# Project.net
KiCad netlist of a schematic drawn in EAGLE
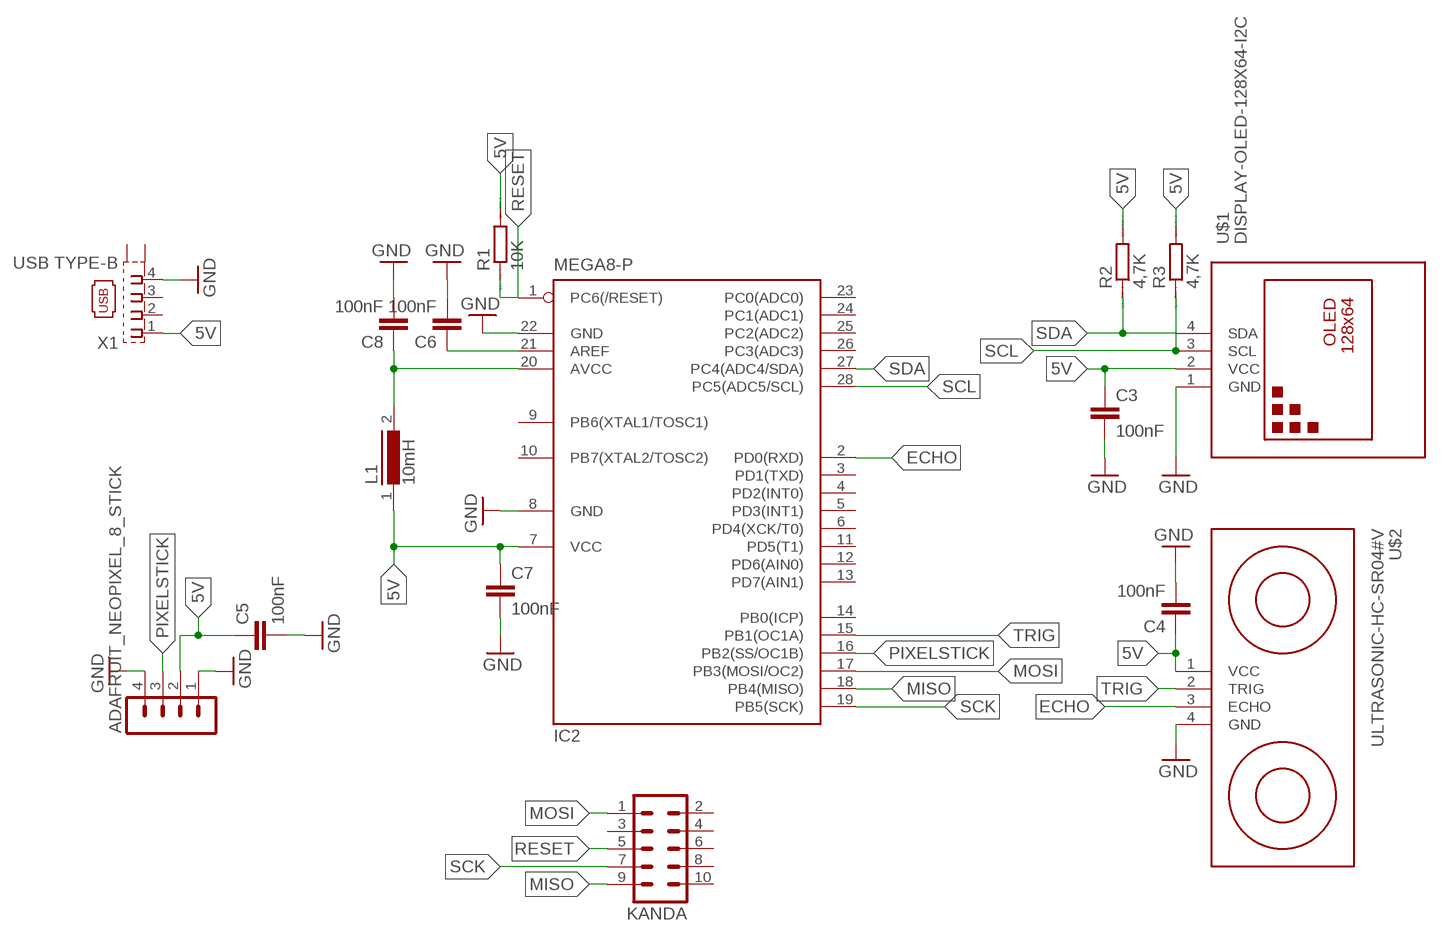
[diagram p0: schematic, sheet 1]

(export (version "E")
  (design (tool "Eeschema 10.0.6"))
  (components
    (comp (ref "ADAFRUIT_NEOPIXEL_8_STICK")
      (value "MA04-1")
      (footprint "eagle-import:MA04-1")
      (libsource (lib "eagle-import") (part "MA04-1"))
    )
    (comp (ref "C3")
      (value "100nF")
      (footprint "eagle-import:C025-024X044")
      (libsource (lib "eagle-import") (part "C-EU025-024X044"))
    )
    (comp (ref "C4")
      (value "100nF")
      (footprint "eagle-import:C025-024X044")
      (libsource (lib "eagle-import") (part "C-EU025-024X044"))
    )
    (comp (ref "C5")
      (value "100nF")
      (footprint "eagle-import:C025-024X044")
      (libsource (lib "eagle-import") (part "C-EU025-024X044"))
    )
    (comp (ref "C6")
      (value "100nF")
      (footprint "eagle-import:C025-024X044")
      (libsource (lib "eagle-import") (part "C-EU025-024X044"))
    )
    (comp (ref "C7")
      (value "100nF")
      (footprint "eagle-import:C025-024X044")
      (libsource (lib "eagle-import") (part "C-EU025-024X044"))
    )
    (comp (ref "C8")
      (value "100nF")
      (footprint "eagle-import:C025-024X044")
      (libsource (lib "eagle-import") (part "C-EU025-024X044"))
    )
    (comp (ref "IC2")
      (value "MEGA8-P")
      (footprint "eagle-import:DIL28-3")
      (libsource (lib "eagle-import") (part "MEGA8-P"))
    )
    (comp (ref "KANDA")
      (value "ML10")
      (footprint "eagle-import:ML10")
      (libsource (lib "eagle-import") (part "ML10"))
    )
    (comp (ref "L1")
      (value "10mH")
      (footprint "eagle-import:A26GFC")
      (libsource (lib "eagle-import") (part "A26GFC"))
    )
    (comp (ref "R1")
      (value "10K")
      (footprint "eagle-import:R0805")
      (libsource (lib "eagle-import") (part "R"))
    )
    (comp (ref "R2")
      (value "4,7K")
      (footprint "eagle-import:R0805")
      (libsource (lib "eagle-import") (part "R"))
    )
    (comp (ref "R3")
      (value "4,7K")
      (footprint "eagle-import:R0805")
      (libsource (lib "eagle-import") (part "R"))
    )
    (comp (ref "U$1")
      (value "DISPLAY-OLED-128X64-I2C")
      (footprint "eagle-import:DISPLAY-OLED-128X64-I2C")
      (libsource (lib "eagle-import") (part "DISPLAY-OLED-128X64-I2C"))
    )
    (comp (ref "U$2")
      (value "ULTRASONIC-HC-SR04#V")
      (footprint "eagle-import:ULTRASONIC-HC-SR04#V")
      (libsource (lib "eagle-import") (part "ULTRASONIC-HC-SR04#V"))
    )
    (comp (ref "X1")
      (value "USB TYPE-B")
      (footprint "eagle-import:KUSBVX-BS1N")
      (libsource (lib "eagle-import") (part "KUSBVX-BS1N"))
    )
  )
  (nets
    (net (code "1") (name "5V") (class "Default")
      (node (ref "ADAFRUIT_NEOPIXEL_8_STICK") (pin "2") (pinfunction "2_2") (pintype "passive"))
      (node (ref "C3") (pin "1") (pinfunction "1_1") (pintype "passive"))
      (node (ref "C4") (pin "1") (pinfunction "1_1") (pintype "passive"))
      (node (ref "C5") (pin "1") (pinfunction "1_1") (pintype "passive"))
      (node (ref "C7") (pin "1") (pinfunction "1_1") (pintype "passive"))
      (node (ref "IC2") (pin "7") (pinfunction "VCC_7") (pintype "power_in"))
      (node (ref "L1") (pin "1") (pinfunction "1_1") (pintype "passive"))
      (node (ref "R1") (pin "2") (pinfunction "2_2") (pintype "passive"))
      (node (ref "R2") (pin "2") (pinfunction "2_2") (pintype "passive"))
      (node (ref "R3") (pin "2") (pinfunction "2_2") (pintype "passive"))
      (node (ref "U$1") (pin "2") (pinfunction "VCC_2") (pintype "power_in"))
      (node (ref "U$2") (pin "1") (pinfunction "VCC_1") (pintype "power_in"))
      (node (ref "X1") (pin "1") (pinfunction "1_1") (pintype "passive"))
    )
    (net (code "2") (name "ECHO") (class "Default")
      (node (ref "IC2") (pin "2") (pinfunction "PD0(RXD)_2") (pintype "bidirectional"))
      (node (ref "U$2") (pin "3") (pinfunction "ECHO_3") (pintype "output"))
    )
    (net (code "3") (name "GND") (class "Default")
      (node (ref "ADAFRUIT_NEOPIXEL_8_STICK") (pin "1") (pinfunction "1_1") (pintype "passive"))
      (node (ref "ADAFRUIT_NEOPIXEL_8_STICK") (pin "4") (pinfunction "4_4") (pintype "passive"))
      (node (ref "C3") (pin "2") (pinfunction "2_2") (pintype "passive"))
      (node (ref "C4") (pin "2") (pinfunction "2_2") (pintype "passive"))
      (node (ref "C5") (pin "2") (pinfunction "2_2") (pintype "passive"))
      (node (ref "C6") (pin "2") (pinfunction "2_2") (pintype "passive"))
      (node (ref "C7") (pin "2") (pinfunction "2_2") (pintype "passive"))
      (node (ref "C8") (pin "2") (pinfunction "2_2") (pintype "passive"))
      (node (ref "IC2") (pin "22") (pinfunction "GND_22") (pintype "power_in"))
      (node (ref "IC2") (pin "8") (pinfunction "GND_8") (pintype "power_in"))
      (node (ref "U$1") (pin "1") (pinfunction "GND_1") (pintype "power_in"))
      (node (ref "U$2") (pin "4") (pinfunction "GND_4") (pintype "power_in"))
      (node (ref "X1") (pin "4") (pinfunction "4_4") (pintype "passive"))
    )
    (net (code "4") (name "MISO") (class "Default")
      (node (ref "IC2") (pin "18") (pinfunction "PB4(MISO)_18") (pintype "bidirectional"))
      (node (ref "KANDA") (pin "9") (pinfunction "9_9") (pintype "passive"))
    )
    (net (code "5") (name "MOSI") (class "Default")
      (node (ref "IC2") (pin "17") (pinfunction "PB3(MOSI/OC2)_17") (pintype "bidirectional"))
      (node (ref "KANDA") (pin "1") (pinfunction "1_1") (pintype "passive"))
    )
    (net (code "6") (name "Net-(IC2-AREF)") (class "Default")
      (node (ref "C6") (pin "1") (pinfunction "1_1") (pintype "passive"))
      (node (ref "IC2") (pin "21") (pinfunction "AREF_21") (pintype "passive"))
    )
    (net (code "7") (name "Net-(IC2-AVCC)") (class "Default")
      (node (ref "C8") (pin "1") (pinfunction "1_1") (pintype "passive"))
      (node (ref "IC2") (pin "20") (pinfunction "AVCC_20") (pintype "power_in"))
      (node (ref "L1") (pin "2") (pinfunction "2_2") (pintype "passive"))
    )
    (net (code "8") (name "PIXELSTICK") (class "Default")
      (node (ref "ADAFRUIT_NEOPIXEL_8_STICK") (pin "3") (pinfunction "3_3") (pintype "passive"))
      (node (ref "IC2") (pin "16") (pinfunction "PB2(SS/OC1B)_16") (pintype "bidirectional"))
    )
    (net (code "9") (name "RESET") (class "Default")
      (node (ref "IC2") (pin "1") (pinfunction "PC6(/RESET)_1") (pintype "bidirectional"))
      (node (ref "KANDA") (pin "5") (pinfunction "5_5") (pintype "passive"))
      (node (ref "R1") (pin "1") (pinfunction "1_1") (pintype "passive"))
    )
    (net (code "10") (name "SCK") (class "Default")
      (node (ref "IC2") (pin "19") (pinfunction "PB5(SCK)_19") (pintype "bidirectional"))
      (node (ref "KANDA") (pin "7") (pinfunction "7_7") (pintype "passive"))
    )
    (net (code "11") (name "SCL") (class "Default")
      (node (ref "IC2") (pin "28") (pinfunction "PC5(ADC5/SCL)_28") (pintype "bidirectional"))
      (node (ref "R3") (pin "1") (pinfunction "1_1") (pintype "passive"))
      (node (ref "U$1") (pin "3") (pinfunction "SCL_3") (pintype "bidirectional"))
    )
    (net (code "12") (name "SDA") (class "Default")
      (node (ref "IC2") (pin "27") (pinfunction "PC4(ADC4/SDA)_27") (pintype "bidirectional"))
      (node (ref "R2") (pin "1") (pinfunction "1_1") (pintype "passive"))
      (node (ref "U$1") (pin "4") (pinfunction "SDA_4") (pintype "bidirectional"))
    )
    (net (code "13") (name "TRIG") (class "Default")
      (node (ref "IC2") (pin "15") (pinfunction "PB1(OC1A)_15") (pintype "bidirectional"))
      (node (ref "U$2") (pin "2") (pinfunction "TRIG_2") (pintype "input"))
    )
    (net (code "14") (name "unconnected-(IC2-PB0(ICP)-Pad14)") (class "Default")
      (node (ref "IC2") (pin "14") (pinfunction "PB0(ICP)_14") (pintype "bidirectional"))
    )
    (net (code "15") (name "unconnected-(IC2-PB6(XTAL1{slash}TOSC1)-Pad9)") (class "Default")
      (node (ref "IC2") (pin "9") (pinfunction "PB6(XTAL1/TOSC1)_9") (pintype "bidirectional"))
    )
    (net (code "16") (name "unconnected-(IC2-PB7(XTAL2{slash}TOSC2)-Pad10)") (class "Default")
      (node (ref "IC2") (pin "10") (pinfunction "PB7(XTAL2/TOSC2)_10") (pintype "bidirectional"))
    )
    (net (code "17") (name "unconnected-(IC2-PC0(ADC0)-Pad23)") (class "Default")
      (node (ref "IC2") (pin "23") (pinfunction "PC0(ADC0)_23") (pintype "bidirectional"))
    )
    (net (code "18") (name "unconnected-(IC2-PC1(ADC1)-Pad24)") (class "Default")
      (node (ref "IC2") (pin "24") (pinfunction "PC1(ADC1)_24") (pintype "bidirectional"))
    )
    (net (code "19") (name "unconnected-(IC2-PC2(ADC2)-Pad25)") (class "Default")
      (node (ref "IC2") (pin "25") (pinfunction "PC2(ADC2)_25") (pintype "bidirectional"))
    )
    (net (code "20") (name "unconnected-(IC2-PC3(ADC3)-Pad26)") (class "Default")
      (node (ref "IC2") (pin "26") (pinfunction "PC3(ADC3)_26") (pintype "bidirectional"))
    )
    (net (code "21") (name "unconnected-(IC2-PD1(TXD)-Pad3)") (class "Default")
      (node (ref "IC2") (pin "3") (pinfunction "PD1(TXD)_3") (pintype "bidirectional"))
    )
    (net (code "22") (name "unconnected-(IC2-PD2(INT0)-Pad4)") (class "Default")
      (node (ref "IC2") (pin "4") (pinfunction "PD2(INT0)_4") (pintype "bidirectional"))
    )
    (net (code "23") (name "unconnected-(IC2-PD3(INT1)-Pad5)") (class "Default")
      (node (ref "IC2") (pin "5") (pinfunction "PD3(INT1)_5") (pintype "bidirectional"))
    )
    (net (code "24") (name "unconnected-(IC2-PD4(XCK{slash}T0)-Pad6)") (class "Default")
      (node (ref "IC2") (pin "6") (pinfunction "PD4(XCK/T0)_6") (pintype "bidirectional"))
    )
    (net (code "25") (name "unconnected-(IC2-PD5(T1)-Pad11)") (class "Default")
      (node (ref "IC2") (pin "11") (pinfunction "PD5(T1)_11") (pintype "bidirectional"))
    )
    (net (code "26") (name "unconnected-(IC2-PD6(AIN0)-Pad12)") (class "Default")
      (node (ref "IC2") (pin "12") (pinfunction "PD6(AIN0)_12") (pintype "bidirectional"))
    )
    (net (code "27") (name "unconnected-(IC2-PD7(AIN1)-Pad13)") (class "Default")
      (node (ref "IC2") (pin "13") (pinfunction "PD7(AIN1)_13") (pintype "bidirectional"))
    )
    (net (code "28") (name "unconnected-(KANDA-Pad2)") (class "Default")
      (node (ref "KANDA") (pin "2") (pinfunction "2_2") (pintype "passive"))
    )
    (net (code "29") (name "unconnected-(KANDA-Pad3)") (class "Default")
      (node (ref "KANDA") (pin "3") (pinfunction "3_3") (pintype "passive"))
    )
    (net (code "30") (name "unconnected-(KANDA-Pad4)") (class "Default")
      (node (ref "KANDA") (pin "4") (pinfunction "4_4") (pintype "passive"))
    )
    (net (code "31") (name "unconnected-(KANDA-Pad6)") (class "Default")
      (node (ref "KANDA") (pin "6") (pinfunction "6_6") (pintype "passive"))
    )
    (net (code "32") (name "unconnected-(KANDA-Pad8)") (class "Default")
      (node (ref "KANDA") (pin "8") (pinfunction "8_8") (pintype "passive"))
    )
    (net (code "33") (name "unconnected-(KANDA-Pad10)") (class "Default")
      (node (ref "KANDA") (pin "10") (pinfunction "10_10") (pintype "passive"))
    )
    (net (code "34") (name "unconnected-(X1-Pad2)") (class "Default")
      (node (ref "X1") (pin "2") (pinfunction "2_2") (pintype "passive"))
    )
    (net (code "35") (name "unconnected-(X1-Pad3)") (class "Default")
      (node (ref "X1") (pin "3") (pinfunction "3_3") (pintype "passive"))
    )
    (net (code "36") (name "unconnected-(X1-S1-PadM1)") (class "Default")
      (node (ref "X1") (pin "M1") (pinfunction "S1_M1") (pintype "passive"))
    )
    (net (code "37") (name "unconnected-(X1-S2-PadM2)") (class "Default")
      (node (ref "X1") (pin "M2") (pinfunction "S2_M2") (pintype "passive"))
    )
  )
)
